# 40M_PA.net
KiCad netlist of a schematic drawn in Altium Designer
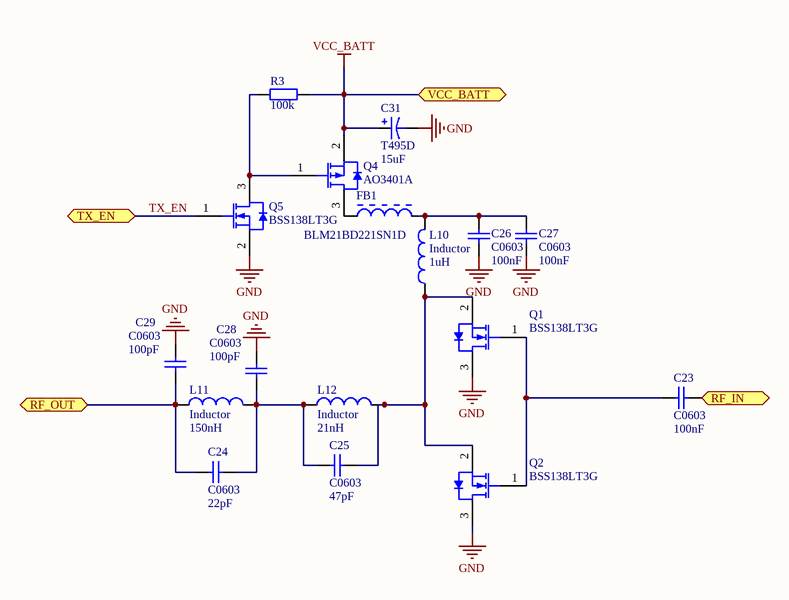
[diagram p0: 40M_PA.SchDoc]

(export (version "E")
  (design (tool "Eeschema 10.0.6"))
  (components
    (comp (ref "C23")
      (value "C0603")
      (footprint "0603")
      (description "Ceramic Chip Capacitor - Standard")
      (fields (field (name "ALTIUM_VALUE") "100nF") (field (name "PUBLISHER") "Altium Limited"))
      (libsource (lib "KEMET Chip Capacitor") (part "C0603"))
    )
    (comp (ref "C24")
      (value "C0603")
      (footprint "0603")
      (description "Ceramic Chip Capacitor - Standard")
      (fields (field (name "ALTIUM_VALUE") "22pF") (field (name "PUBLISHER") "Altium Limited"))
      (libsource (lib "KEMET Chip Capacitor") (part "C0603"))
    )
    (comp (ref "C25")
      (value "C0603")
      (footprint "0603")
      (description "Ceramic Chip Capacitor - Standard")
      (fields (field (name "ALTIUM_VALUE") "47pF") (field (name "PUBLISHER") "Altium Limited"))
      (libsource (lib "KEMET Chip Capacitor") (part "C0603"))
    )
    (comp (ref "C26")
      (value "C0603")
      (footprint "0603")
      (description "Ceramic Chip Capacitor - Standard")
      (fields (field (name "ALTIUM_VALUE") "100nF") (field (name "PUBLISHER") "Altium Limited"))
      (libsource (lib "KEMET Chip Capacitor") (part "C0603"))
    )
    (comp (ref "C27")
      (value "C0603")
      (footprint "0603")
      (description "Ceramic Chip Capacitor - Standard")
      (fields (field (name "ALTIUM_VALUE") "100nF") (field (name "PUBLISHER") "Altium Limited"))
      (libsource (lib "KEMET Chip Capacitor") (part "C0603"))
    )
    (comp (ref "C28")
      (value "C0603")
      (footprint "0603")
      (description "Ceramic Chip Capacitor - Standard")
      (fields (field (name "ALTIUM_VALUE") "100pF") (field (name "PUBLISHER") "Altium Limited"))
      (libsource (lib "KEMET Chip Capacitor") (part "C0603"))
    )
    (comp (ref "C29")
      (value "C0603")
      (footprint "0603")
      (description "Ceramic Chip Capacitor - Standard")
      (fields (field (name "ALTIUM_VALUE") "100pF") (field (name "PUBLISHER") "Altium Limited"))
      (libsource (lib "KEMET Chip Capacitor") (part "C0603"))
    )
    (comp (ref "C31")
      (value "T495D")
      (footprint "D")
      (description "Solid Tantalum Chip Capacitor, Standard T495 Series - Low ESR, Surge Robust")
      (fields (field (name "ALTIUM_VALUE") "15uF") (field (name "PUBLISHER") "Altium Limited"))
      (libsource (lib "KEMET Chip Capacitor") (part "T495D"))
    )
    (comp (ref "FB1")
      (value "BLM21BD221SN1D")
      (footprint "MURA-BLM21-H1-CHIP-2_V")
      (fields (field (name "MANUFACTURER") "Murata"))
      (libsource (lib "Altium Content Vault") (part "MURA-FB-2"))
    )
    (comp (ref "L10")
      (value "Inductor")
      (footprint "INDC1608L")
      (fields (field (name "ALTIUM_VALUE") "1uH") (field (name "PUBLISHER") "Altium Limited"))
      (libsource (lib "Miscellaneous Devices") (part "Inductor"))
    )
    (comp (ref "L11")
      (value "Inductor")
      (footprint "INDC1608L")
      (fields (field (name "ALTIUM_VALUE") "150nH") (field (name "PUBLISHER") "Altium Limited"))
      (libsource (lib "Miscellaneous Devices") (part "Inductor"))
    )
    (comp (ref "L12")
      (value "Inductor")
      (footprint "INDC1608L")
      (fields (field (name "ALTIUM_VALUE") "21nH") (field (name "PUBLISHER") "Altium Limited"))
      (libsource (lib "Miscellaneous Devices") (part "Inductor"))
    )
    (comp (ref "Q1")
      (value "BSS138LT3G")
      (footprint "ONSC-SOT-23-3-318-08_V")
      (description "Power MOSFET, 200 mA, 50 V, N-Channel, 3-Pin SOT-23, Pb-Free, Tape and Reel")
      (fields (field (name "MANUFACTURER") "On Semiconductor"))
      (libsource (lib "Altium Content Vault") (part "ONSC-NMOS-G1S2D3-3"))
    )
    (comp (ref "Q2")
      (value "BSS138LT3G")
      (footprint "ONSC-SOT-23-3-318-08_V")
      (description "Power MOSFET, 200 mA, 50 V, N-Channel, 3-Pin SOT-23, Pb-Free, Tape and Reel")
      (fields (field (name "MANUFACTURER") "On Semiconductor"))
      (libsource (lib "Altium Content Vault") (part "ONSC-NMOS-G1S2D3-3"))
    )
    (comp (ref "Q4")
      (value "AO3401A")
      (footprint "AO-SOT-23-3L_V")
      (description "P-Channel MOSFET, 30 V, 4 A, -55 to 150 degC, 3-Pin SOT-23-3L, RoHS, Tape and Reel")
      (fields (field (name "MANUFACTURER") "Alpha and Omega"))
      (libsource (lib "Altium Content Vault") (part "PEMOS-GSD-3"))
    )
    (comp (ref "Q5")
      (value "BSS138LT3G")
      (footprint "ONSC-SOT-23-3-318-08_V")
      (description "Power MOSFET, 200 mA, 50 V, N-Channel, 3-Pin SOT-23, Pb-Free, Tape and Reel")
      (fields (field (name "MANUFACTURER") "On Semiconductor"))
      (libsource (lib "Altium Content Vault") (part "CMP-1058-00765-1"))
    )
    (comp (ref "R3") (value "100k") (footprint "R0603") (libsource (lib "ftg_lib") (part "1k 0603")))
  )
  (nets
    (net (code "1") (name "/RF_IN") (class "Default")
      (node (ref "C23") (pin "2") (pinfunction "2_2") (pintype "passive"))
    )
    (net (code "2") (name "/RF_OUT") (class "Default")
      (node (ref "C24") (pin "1") (pinfunction "1_1") (pintype "passive"))
      (node (ref "C29") (pin "2") (pinfunction "2_2") (pintype "passive"))
      (node (ref "L11") (pin "1") (pinfunction "1_1") (pintype "passive"))
    )
    (net (code "3") (name "/TX_EN") (class "Default")
      (node (ref "Q5") (pin "1") (pinfunction "G_1") (pintype "passive"))
    )
    (net (code "4") (name "GND") (class "Default")
      (node (ref "C26") (pin "2") (pinfunction "2_2") (pintype "passive"))
      (node (ref "C27") (pin "2") (pinfunction "2_2") (pintype "passive"))
      (node (ref "C28") (pin "1") (pinfunction "1_1") (pintype "passive"))
      (node (ref "C29") (pin "1") (pinfunction "1_1") (pintype "passive"))
      (node (ref "C31") (pin "2") (pinfunction "2_2") (pintype "passive"))
      (node (ref "Q1") (pin "3") (pinfunction "D_3") (pintype "passive"))
      (node (ref "Q2") (pin "3") (pinfunction "D_3") (pintype "passive"))
      (node (ref "Q5") (pin "2") (pinfunction "S_2") (pintype "passive"))
    )
    (net (code "5") (name "Net-(C24-Pad2)") (class "Default")
      (node (ref "C24") (pin "2") (pinfunction "2_2") (pintype "passive"))
      (node (ref "C25") (pin "1") (pinfunction "1_1") (pintype "passive"))
      (node (ref "C28") (pin "2") (pinfunction "2_2") (pintype "passive"))
      (node (ref "L11") (pin "2") (pinfunction "2_2") (pintype "passive"))
      (node (ref "L12") (pin "1") (pinfunction "1_1") (pintype "passive"))
    )
    (net (code "6") (name "Net-(C26-Pad1)") (class "Default")
      (node (ref "C26") (pin "1") (pinfunction "1_1") (pintype "passive"))
      (node (ref "C27") (pin "1") (pinfunction "1_1") (pintype "passive"))
      (node (ref "FB1") (pin "2") (pinfunction "2_2") (pintype "passive"))
      (node (ref "L10") (pin "2") (pinfunction "2_2") (pintype "passive"))
    )
    (net (code "7") (name "Net-(Q1-G)") (class "Default")
      (node (ref "C23") (pin "1") (pinfunction "1_1") (pintype "passive"))
      (node (ref "Q1") (pin "1") (pinfunction "G_1") (pintype "passive"))
      (node (ref "Q2") (pin "1") (pinfunction "G_1") (pintype "passive"))
    )
    (net (code "8") (name "Net-(Q1-S)") (class "Default")
      (node (ref "C25") (pin "2") (pinfunction "2_2") (pintype "passive"))
      (node (ref "L10") (pin "1") (pinfunction "1_1") (pintype "passive"))
      (node (ref "L12") (pin "2") (pinfunction "2_2") (pintype "passive"))
      (node (ref "Q1") (pin "2") (pinfunction "S_2") (pintype "passive"))
      (node (ref "Q2") (pin "2") (pinfunction "S_2") (pintype "passive"))
    )
    (net (code "9") (name "Net-(Q4-DRAIN)") (class "Default")
      (node (ref "FB1") (pin "1") (pinfunction "1_1") (pintype "passive"))
      (node (ref "Q4") (pin "3") (pinfunction "DRAIN_3") (pintype "passive"))
    )
    (net (code "10") (name "Net-(Q4-GATE)") (class "Default")
      (node (ref "Q4") (pin "1") (pinfunction "GATE_1") (pintype "passive"))
      (node (ref "Q5") (pin "3") (pinfunction "D_3") (pintype "passive"))
      (node (ref "R3") (pin "1") (pinfunction "1_1") (pintype "passive"))
    )
    (net (code "11") (name "VCC_BATT") (class "Default")
      (node (ref "C31") (pin "1") (pinfunction "1_1") (pintype "passive"))
      (node (ref "Q4") (pin "2") (pinfunction "SOURCE_2") (pintype "passive"))
      (node (ref "R3") (pin "2") (pinfunction "2_2") (pintype "passive"))
    )
  )
)
